# OLEDMiniFlyMCU.net
KiCad netlist of a schematic drawn in Altium Designer
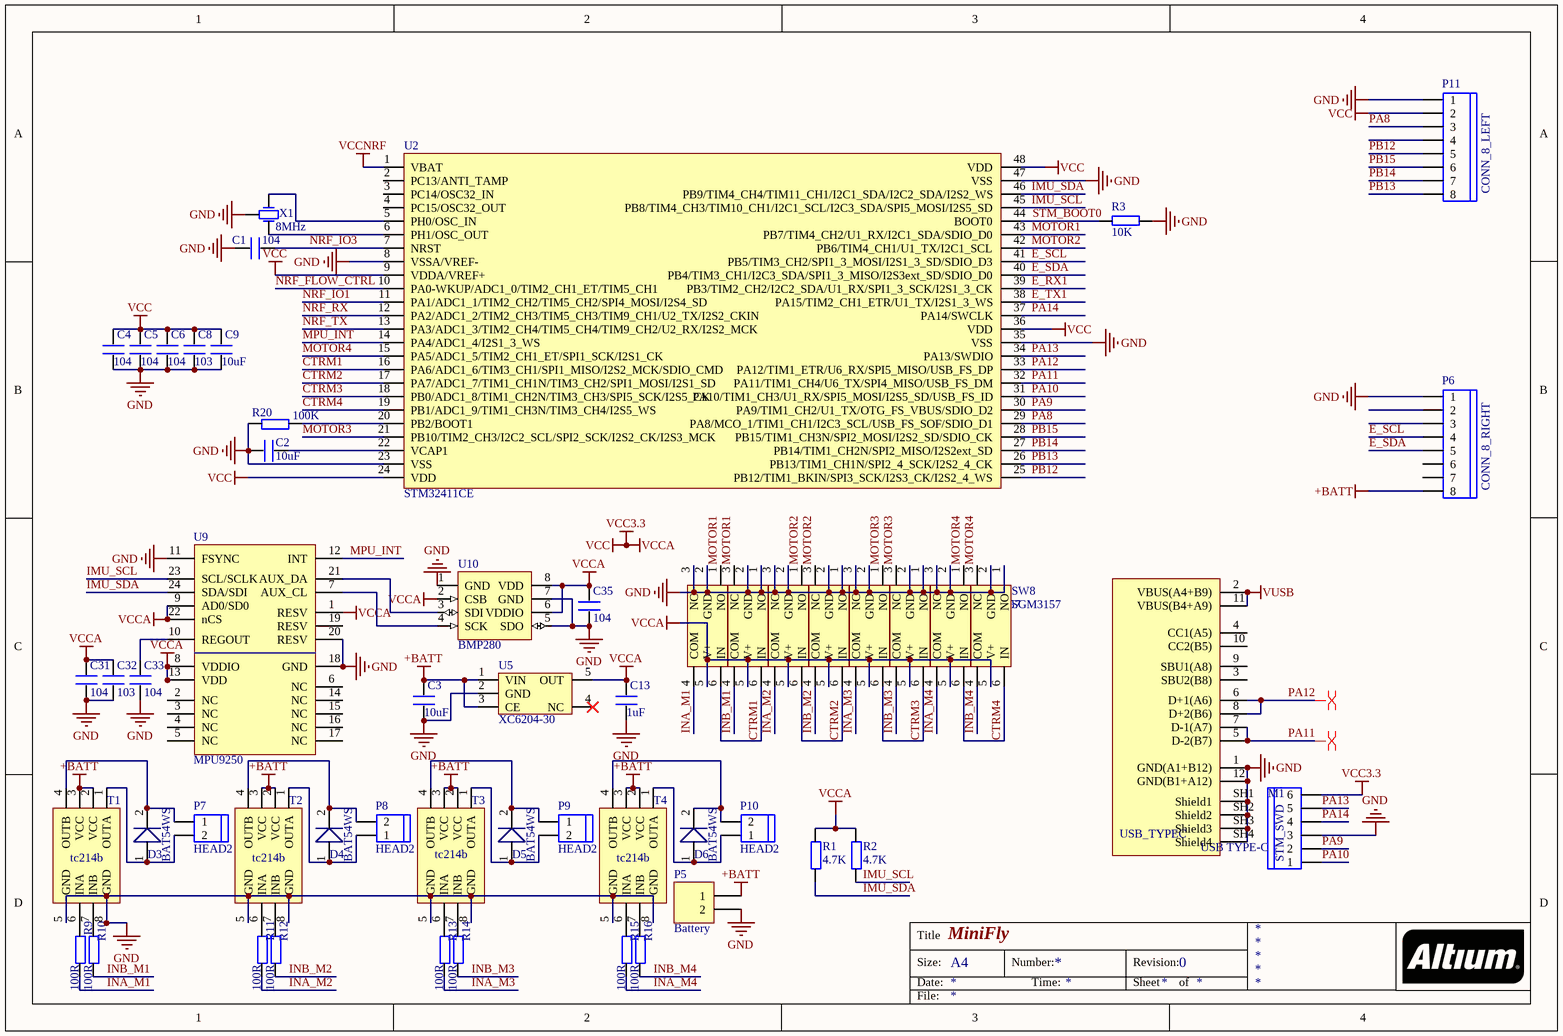
[diagram p0: OLEDMiniFlyMCU.SchDoc]

(export (version "E")
  (design (tool "Eeschema 10.0.6"))
  (components
    (comp (ref "C1") (value "104") (footprint "C 0603_L") (libsource (lib "ATK-2014-09-12") (part "C")))
    (comp (ref "C2") (value "10uF") (footprint "C 0603_L") (libsource (lib "ATK-2014-09-12") (part "C")))
    (comp (ref "C3") (value "10uF") (footprint "C 0603_L") (libsource (lib "ATK-2014-09-12") (part "C")))
    (comp (ref "C4") (value "104") (footprint "C 0603_L") (libsource (lib "ATK-2014-09-12") (part "C")))
    (comp (ref "C5") (value "104") (footprint "C 0603_L") (libsource (lib "ATK-2014-09-12") (part "C")))
    (comp (ref "C6") (value "104") (footprint "C 0603_L") (libsource (lib "ATK-2014-09-12") (part "C")))
    (comp (ref "C8") (value "103") (footprint "C 0603_L") (libsource (lib "ATK-2014-09-12") (part "C")))
    (comp (ref "C9") (value "10uF") (footprint "C 0603_L") (libsource (lib "ATK-2014-09-12") (part "C")))
    (comp (ref "C13") (value "1uF") (footprint "C 0603_L") (libsource (lib "ATK-2014-09-12") (part "C")))
    (comp (ref "C31") (value "104") (footprint "C 0603_L") (libsource (lib "ATK-2014-09-12") (part "C")))
    (comp (ref "C32") (value "103") (footprint "C 0603_L") (libsource (lib "ATK-2014-09-12") (part "C")))
    (comp (ref "C33") (value "104") (footprint "C 0603_L") (libsource (lib "ATK-2014-09-12") (part "C")))
    (comp (ref "C35") (value "104") (footprint "C 0603_L") (libsource (lib "ATK-2014-09-12") (part "C")))
    (comp (ref "D3")
      (value "BAT54WS")
      (footprint "SOD-323")
      (description "单肖特基二极管")
      (libsource (lib "ATK-2014-09-12") (part "BAT54"))
    )
    (comp (ref "D4")
      (value "BAT54WS")
      (footprint "SOD-323")
      (description "单肖特基二极管")
      (libsource (lib "ATK-2014-09-12") (part "BAT54"))
    )
    (comp (ref "D5")
      (value "BAT54WS")
      (footprint "SOD-323")
      (description "单肖特基二极管")
      (libsource (lib "ATK-2014-09-12") (part "BAT54"))
    )
    (comp (ref "D6")
      (value "BAT54WS")
      (footprint "SOD-323")
      (description "单肖特基二极管")
      (libsource (lib "ATK-2014-09-12") (part "BAT54"))
    )
    (comp (ref "M1") (value "STM_SWD") (footprint "SH1.0_6P") (libsource (lib "MiniFly ") (part "HEAD6")))
    (comp (ref "P5")
      (value "Battery")
      (footprint "HDR1X2")
      (description "Header, 2-Pin")
      (fields (field (name "PUBLISHER") "Altium Limited"))
      (libsource (lib "Miscellaneous Connectors") (part "Header 2"))
    )
    (comp (ref "P6")
      (value "CONN_8_RIGHT")
      (footprint "HEADER8-2.0MM")
      (libsource (lib "ATK-2014-09-12") (part "HEAD8"))
    )
    (comp (ref "P7")
      (value "HEAD2")
      (footprint "HEADER2-1.25MM")
      (libsource (lib "ATK-2014-09-12") (part "HEAD2"))
    )
    (comp (ref "P8")
      (value "HEAD2")
      (footprint "HEADER2-1.25MM")
      (libsource (lib "ATK-2014-09-12") (part "HEAD2"))
    )
    (comp (ref "P9")
      (value "HEAD2")
      (footprint "HEADER2-1.25MM")
      (libsource (lib "ATK-2014-09-12") (part "HEAD2"))
    )
    (comp (ref "P10")
      (value "HEAD2")
      (footprint "HEADER2-1.25MM")
      (libsource (lib "ATK-2014-09-12") (part "HEAD2"))
    )
    (comp (ref "P11")
      (value "CONN_8_LEFT")
      (footprint "HEADER8-2.0MM")
      (libsource (lib "ATK-2014-09-12") (part "HEAD8"))
    )
    (comp (ref "R1") (value "4.7K") (footprint "R 0603_L") (libsource (lib "ATK-2014-09-12") (part "R")))
    (comp (ref "R2") (value "4.7K") (footprint "R 0603_L") (libsource (lib "ATK-2014-09-12") (part "R")))
    (comp (ref "R3") (value "10K") (footprint "R 0603_L") (libsource (lib "ATK-2014-09-12") (part "R")))
    (comp (ref "R9") (value "100R") (footprint "R 0603_L") (libsource (lib "ATK-2014-09-12") (part "R")))
    (comp (ref "R10") (value "100R") (footprint "R 0603_L") (libsource (lib "ATK-2014-09-12") (part "R")))
    (comp (ref "R11") (value "100R") (footprint "R 0603_L") (libsource (lib "ATK-2014-09-12") (part "R")))
    (comp (ref "R12") (value "100R") (footprint "R 0603_L") (libsource (lib "ATK-2014-09-12") (part "R")))
    (comp (ref "R13") (value "100R") (footprint "R 0603_L") (libsource (lib "ATK-2014-09-12") (part "R")))
    (comp (ref "R14") (value "100R") (footprint "R 0603_L") (libsource (lib "ATK-2014-09-12") (part "R")))
    (comp (ref "R15") (value "100R") (footprint "R 0603_L") (libsource (lib "ATK-2014-09-12") (part "R")))
    (comp (ref "R16") (value "100R") (footprint "R 0603_L") (libsource (lib "ATK-2014-09-12") (part "R")))
    (comp (ref "R20") (value "100K") (footprint "R 0603_L") (libsource (lib "ATK-2014-09-12") (part "R")))
    (comp (ref "SW1")
      (value "SGM3157")
      (footprint "SOT363-6L")
      (description "单路双掷模拟开关")
      (libsource (lib "LovelessingSch") (part "SGM3157"))
    )
    (comp (ref "SW2")
      (value "SGM3157")
      (footprint "SOT363-6L")
      (description "单路双掷模拟开关")
      (libsource (lib "LovelessingSch") (part "SGM3157"))
    )
    (comp (ref "SW3")
      (value "SGM3157")
      (footprint "SOT363-6L")
      (description "单路双掷模拟开关")
      (libsource (lib "LovelessingSch") (part "SGM3157"))
    )
    (comp (ref "SW4")
      (value "SGM3157")
      (footprint "SOT363-6L")
      (description "单路双掷模拟开关")
      (libsource (lib "LovelessingSch") (part "SGM3157"))
    )
    (comp (ref "SW5")
      (value "SGM3157")
      (footprint "SOT363-6L")
      (description "单路双掷模拟开关")
      (libsource (lib "LovelessingSch") (part "SGM3157"))
    )
    (comp (ref "SW6")
      (value "SGM3157")
      (footprint "SOT363-6L")
      (description "单路双掷模拟开关")
      (libsource (lib "LovelessingSch") (part "SGM3157"))
    )
    (comp (ref "SW7")
      (value "SGM3157")
      (footprint "SOT363-6L")
      (description "单路双掷模拟开关")
      (libsource (lib "LovelessingSch") (part "SGM3157"))
    )
    (comp (ref "SW8")
      (value "SGM3157")
      (footprint "SOT363-6L")
      (description "单路双掷模拟开关")
      (libsource (lib "LovelessingSch") (part "SGM3157"))
    )
    (comp (ref "T1")
      (value "tc214b")
      (footprint "SOP8_L")
      (description "马达驱动芯片")
      (libsource (lib "LovelessingSch") (part "tc214b"))
    )
    (comp (ref "T2")
      (value "tc214b")
      (footprint "SOP8_L")
      (description "马达驱动芯片")
      (libsource (lib "LovelessingSch") (part "tc214b"))
    )
    (comp (ref "T3")
      (value "tc214b")
      (footprint "SOP8_L")
      (description "马达驱动芯片")
      (libsource (lib "LovelessingSch") (part "tc214b"))
    )
    (comp (ref "T4")
      (value "tc214b")
      (footprint "SOP8_L")
      (description "马达驱动芯片")
      (libsource (lib "LovelessingSch") (part "tc214b"))
    )
    (comp (ref "U2")
      (value "STM32411CE")
      (footprint "UFQFPN48")
      (description "STM32411xC_xE")
      (libsource (lib "ATK-2014-09-12") (part "STM32F411xC_xE"))
    )
    (comp (ref "U5")
      (value "XC6204-30")
      (footprint "SOT23-5L")
      (libsource (lib "ATK-2014-09-12") (part "XC6204"))
    )
    (comp (ref "U9")
      (value "MPU9250")
      (footprint "MPU9250")
      (description "9轴陀螺仪")
      (libsource (lib "LovelessingSch") (part "MPU9250"))
    )
    (comp (ref "U10")
      (value "BMP280")
      (footprint "LGA-8")
      (description "气压传感器")
      (libsource (lib "LovelessingSch") (part "BMP280"))
    )
    (comp (ref "USB_TYPEC")
      (value "USB TypeC")
      (footprint "USB Type-C")
      (description "12P TypeC 母座")
      (libsource (lib "ESP32_Weather") (part "USB Type-C"))
    )
    (comp (ref "X1")
      (value "8MHz")
      (footprint "XTAL-3215-3P")
      (libsource (lib "ATK-2014-09-12") (part "XTAL-3215"))
    )
  )
  (nets
    (net (code "1") (name "+BATT") (class "Default")
      (node (ref "C3") (pin "2") (pintype "passive"))
      (node (ref "P5") (pin "1") (pinfunction "1_1") (pintype "passive"))
      (node (ref "P6") (pin "8") (pinfunction "8_8") (pintype "passive"))
      (node (ref "T1") (pin "2") (pinfunction "VCC_2") (pintype "passive"))
      (node (ref "T1") (pin "3") (pinfunction "VCC_3") (pintype "passive"))
      (node (ref "T2") (pin "2") (pinfunction "VCC_2") (pintype "passive"))
      (node (ref "T2") (pin "3") (pinfunction "VCC_3") (pintype "passive"))
      (node (ref "T3") (pin "2") (pinfunction "VCC_2") (pintype "passive"))
      (node (ref "T3") (pin "3") (pinfunction "VCC_3") (pintype "passive"))
      (node (ref "T4") (pin "2") (pinfunction "VCC_2") (pintype "passive"))
      (node (ref "T4") (pin "3") (pinfunction "VCC_3") (pintype "passive"))
      (node (ref "U5") (pin "1") (pinfunction "VIN_1") (pintype "passive"))
      (node (ref "U5") (pin "3") (pinfunction "CE_3") (pintype "passive"))
    )
    (net (code "2") (name "/CTRM1") (class "Default")
      (node (ref "SW1") (pin "6") (pinfunction "IN_6") (pintype "passive"))
      (node (ref "SW2") (pin "6") (pinfunction "IN_6") (pintype "passive"))
      (node (ref "U2") (pin "16") (pinfunction "PA6/ADC1_6/TIM3_CH1/SPI1_MISO/I2S2_MCK/SDIO_CMD_16") (pintype "passive"))
    )
    (net (code "3") (name "/CTRM2") (class "Default")
      (node (ref "SW3") (pin "6") (pinfunction "IN_6") (pintype "passive"))
      (node (ref "SW4") (pin "6") (pinfunction "IN_6") (pintype "passive"))
      (node (ref "U2") (pin "17") (pinfunction "PA7/ADC1_7/TIM1_CH1N/TIM3_CH2/SPI1_MOSI/I2S1_SD_17") (pintype "passive"))
    )
    (net (code "4") (name "/CTRM3") (class "Default")
      (node (ref "SW5") (pin "6") (pinfunction "IN_6") (pintype "passive"))
      (node (ref "SW6") (pin "6") (pinfunction "IN_6") (pintype "passive"))
      (node (ref "U2") (pin "18") (pinfunction "PB0/ADC1_8/TIM1_CH2N/TIM3_CH3/SPI5_SCK/I2S5_CK_18") (pintype "passive"))
    )
    (net (code "5") (name "/CTRM4") (class "Default")
      (node (ref "SW7") (pin "6") (pinfunction "IN_6") (pintype "passive"))
      (node (ref "SW8") (pin "6") (pinfunction "IN_6") (pintype "passive"))
      (node (ref "U2") (pin "19") (pinfunction "PB1/ADC1_9/TIM1_CH3N/TIM3_CH4/I2S5_WS_19") (pintype "passive"))
    )
    (net (code "6") (name "/E_RX1") (class "Default")
      (node (ref "U2") (pin "39") (pinfunction "PB3/TIM2_CH2/I2C2_SDA/U1_RX/SPI1_3_SCK/I2S1_3_CK_39") (pintype "passive"))
    )
    (net (code "7") (name "/E_SCL") (class "Default")
      (node (ref "P6") (pin "4") (pinfunction "4_4") (pintype "passive"))
      (node (ref "U2") (pin "41") (pinfunction "PB5/TIM3_CH2/SPI1_3_MOSI/I2S1_3_SD/SDIO_D3_41") (pintype "passive"))
    )
    (net (code "8") (name "/E_SDA") (class "Default")
      (node (ref "P6") (pin "5") (pinfunction "5_5") (pintype "passive"))
      (node (ref "U2") (pin "40") (pinfunction "PB4/TIM3_CH1/I2C3_SDA/SPI1_3_MISO/I2S3ext_SD/SDIO_D0_40") (pintype "passive"))
    )
    (net (code "9") (name "/E_TX1") (class "Default")
      (node (ref "U2") (pin "38") (pinfunction "PA15/TIM2_CH1_ETR/U1_TX/I2S1_3_WS_38") (pintype "passive"))
    )
    (net (code "10") (name "/IMU_SCL") (class "Default")
      (node (ref "R2") (pin "1") (pintype "passive"))
      (node (ref "U2") (pin "45") (pinfunction "PB8/TIM4_CH3/TIM10_CH1/I2C1_SCL/I2C3_SDA/SPI5_MOSI/I2S5_SD_45") (pintype "passive"))
      (node (ref "U9") (pin "23") (pinfunction "SCL/SCLK_23") (pintype "passive"))
    )
    (net (code "11") (name "/IMU_SDA") (class "Default")
      (node (ref "R1") (pin "1") (pintype "passive"))
      (node (ref "U2") (pin "46") (pinfunction "PB9/TIM4_CH4/TIM11_CH1/I2C1_SDA/I2C2_SDA/I2S2_WS_46") (pintype "passive"))
      (node (ref "U9") (pin "24") (pinfunction "SDA/SDI_24") (pintype "passive"))
    )
    (net (code "12") (name "/INA_M1") (class "Default")
      (node (ref "R9") (pin "1") (pintype "passive"))
      (node (ref "SW1") (pin "4") (pinfunction "COM_4") (pintype "passive"))
    )
    (net (code "13") (name "/INA_M2") (class "Default")
      (node (ref "R11") (pin "1") (pintype "passive"))
      (node (ref "SW3") (pin "4") (pinfunction "COM_4") (pintype "passive"))
    )
    (net (code "14") (name "/INA_M3") (class "Default")
      (node (ref "R13") (pin "1") (pintype "passive"))
      (node (ref "SW5") (pin "4") (pinfunction "COM_4") (pintype "passive"))
    )
    (net (code "15") (name "/INA_M4") (class "Default")
      (node (ref "R15") (pin "1") (pintype "passive"))
      (node (ref "SW7") (pin "4") (pinfunction "COM_4") (pintype "passive"))
    )
    (net (code "16") (name "/INB_M1") (class "Default")
      (node (ref "R10") (pin "1") (pintype "passive"))
      (node (ref "SW2") (pin "4") (pinfunction "COM_4") (pintype "passive"))
    )
    (net (code "17") (name "/INB_M2") (class "Default")
      (node (ref "R12") (pin "1") (pintype "passive"))
      (node (ref "SW4") (pin "4") (pinfunction "COM_4") (pintype "passive"))
    )
    (net (code "18") (name "/INB_M3") (class "Default")
      (node (ref "R14") (pin "1") (pintype "passive"))
      (node (ref "SW6") (pin "4") (pinfunction "COM_4") (pintype "passive"))
    )
    (net (code "19") (name "/INB_M4") (class "Default")
      (node (ref "R16") (pin "1") (pintype "passive"))
      (node (ref "SW8") (pin "4") (pinfunction "COM_4") (pintype "passive"))
    )
    (net (code "20") (name "/MOTOR1") (class "Default")
      (node (ref "SW1") (pin "1") (pinfunction "NO_1") (pintype "passive"))
      (node (ref "SW2") (pin "3") (pinfunction "NC_3") (pintype "passive"))
      (node (ref "U2") (pin "43") (pinfunction "PB7/TIM4_CH2/U1_RX/I2C1_SDA/SDIO_D0_43") (pintype "passive"))
    )
    (net (code "21") (name "/MOTOR2") (class "Default")
      (node (ref "SW3") (pin "1") (pinfunction "NO_1") (pintype "passive"))
      (node (ref "SW4") (pin "3") (pinfunction "NC_3") (pintype "passive"))
      (node (ref "U2") (pin "42") (pinfunction "PB6/TIM4_CH1/U1_TX/I2C1_SCL_42") (pintype "passive"))
    )
    (net (code "22") (name "/MOTOR3") (class "Default")
      (node (ref "SW5") (pin "1") (pinfunction "NO_1") (pintype "passive"))
      (node (ref "SW6") (pin "3") (pinfunction "NC_3") (pintype "passive"))
      (node (ref "U2") (pin "21") (pinfunction "PB10/TIM2_CH3/I2C2_SCL/SPI2_SCK/I2S2_CK/I2S3_MCK_21") (pintype "passive"))
    )
    (net (code "23") (name "/MOTOR4") (class "Default")
      (node (ref "SW7") (pin "1") (pinfunction "NO_1") (pintype "passive"))
      (node (ref "SW8") (pin "3") (pinfunction "NC_3") (pintype "passive"))
      (node (ref "U2") (pin "15") (pinfunction "PA5/ADC1_5/TIM2_CH1_ET/SPI1_SCK/I2S1_CK_15") (pintype "passive"))
    )
    (net (code "24") (name "/MPU_INT") (class "Default")
      (node (ref "U2") (pin "14") (pinfunction "PA4/ADC1_4/I2S1_3_WS_14") (pintype "passive"))
      (node (ref "U9") (pin "12") (pinfunction "INT_12") (pintype "passive"))
    )
    (net (code "25") (name "/NRF_FLOW_CTRL") (class "Default")
      (node (ref "U2") (pin "10") (pinfunction "PA0-WKUP/ADC1_0/TIM2_CH1_ET/TIM5_CH1_10") (pintype "passive"))
    )
    (net (code "26") (name "/NRF_IO1") (class "Default")
      (node (ref "U2") (pin "11") (pinfunction "PA1/ADC1_1/TIM2_CH2/TIM5_CH2/SPI4_MOSI/I2S4_SD_11") (pintype "passive"))
    )
    (net (code "27") (name "/NRF_IO3") (class "Default")
      (node (ref "C1") (pin "1") (pintype "passive"))
      (node (ref "U2") (pin "7") (pinfunction "NRST_7") (pintype "passive"))
    )
    (net (code "28") (name "/NRF_RX") (class "Default")
      (node (ref "U2") (pin "12") (pinfunction "PA2/ADC1_2/TIM2_CH3/TIM5_CH3/TIM9_CH1/U2_TX/I2S2_CKIN_12") (pintype "passive"))
    )
    (net (code "29") (name "/NRF_TX") (class "Default")
      (node (ref "U2") (pin "13") (pinfunction "PA3/ADC1_3/TIM2_CH4/TIM5_CH4/TIM9_CH2/U2_RX/I2S2_MCK_13") (pintype "passive"))
    )
    (net (code "30") (name "/PA8") (class "Default")
      (node (ref "P11") (pin "3") (pinfunction "3_3") (pintype "passive"))
      (node (ref "U2") (pin "29") (pinfunction "PA8/MCO_1/TIM1_CH1/I2C3_SCL/USB_FS_SOF/SDIO_D1_29") (pintype "passive"))
    )
    (net (code "31") (name "/PA9") (class "Default")
      (node (ref "M1") (pin "2") (pinfunction "2_2") (pintype "passive"))
      (node (ref "U2") (pin "30") (pinfunction "PA9/TIM1_CH2/U1_TX/OTG_FS_VBUS/SDIO_D2_30") (pintype "passive"))
    )
    (net (code "32") (name "/PA10") (class "Default")
      (node (ref "M1") (pin "1") (pinfunction "1_1") (pintype "passive"))
      (node (ref "U2") (pin "31") (pinfunction "PA10/TIM1_CH3/U1_RX/SPI5_MOSI/I2S5_SD/USB_FS_ID_31") (pintype "passive"))
    )
    (net (code "33") (name "/PA11") (class "Default")
      (node (ref "U2") (pin "32") (pinfunction "PA11/TIM1_CH4/U6_TX/SPI4_MISO/USB_FS_DM_32") (pintype "passive"))
      (node (ref "USB_TYPEC") (pin "5") (pinfunction "D-2(B7)_5") (pintype "passive"))
      (node (ref "USB_TYPEC") (pin "7") (pinfunction "D-1(A7)_7") (pintype "passive"))
    )
    (net (code "34") (name "/PA12") (class "Default")
      (node (ref "U2") (pin "33") (pinfunction "PA12/TIM1_ETR/U6_RX/SPI5_MISO/USB_FS_DP_33") (pintype "passive"))
      (node (ref "USB_TYPEC") (pin "6") (pinfunction "D+1(A6)_6") (pintype "passive"))
      (node (ref "USB_TYPEC") (pin "8") (pinfunction "D+2(B6)_8") (pintype "passive"))
    )
    (net (code "35") (name "/PA13") (class "Default")
      (node (ref "M1") (pin "5") (pinfunction "5_5") (pintype "passive"))
      (node (ref "U2") (pin "34") (pinfunction "PA13/SWDIO_34") (pintype "passive"))
    )
    (net (code "36") (name "/PA14") (class "Default")
      (node (ref "M1") (pin "4") (pinfunction "4_4") (pintype "passive"))
      (node (ref "U2") (pin "37") (pinfunction "PA14/SWCLK_37") (pintype "passive"))
    )
    (net (code "37") (name "/PB12") (class "Default")
      (node (ref "P11") (pin "5") (pinfunction "5_5") (pintype "passive"))
      (node (ref "U2") (pin "25") (pinfunction "PB12/TIM1_BKIN/SPI3_SCK/I2S3_CK/I2S2_4_WS_25") (pintype "passive"))
    )
    (net (code "38") (name "/PB13") (class "Default")
      (node (ref "P11") (pin "8") (pinfunction "8_8") (pintype "passive"))
      (node (ref "U2") (pin "26") (pinfunction "PB13/TIM1_CH1N/SPI2_4_SCK/I2S2_4_CK_26") (pintype "passive"))
    )
    (net (code "39") (name "/PB14") (class "Default")
      (node (ref "P11") (pin "7") (pinfunction "7_7") (pintype "passive"))
      (node (ref "U2") (pin "27") (pinfunction "PB14/TIM1_CH2N/SPI2_MISO/I2S2ext_SD_27") (pintype "passive"))
    )
    (net (code "40") (name "/PB15") (class "Default")
      (node (ref "P11") (pin "6") (pinfunction "6_6") (pintype "passive"))
      (node (ref "U2") (pin "28") (pinfunction "PB15/TIM1_CH3N/SPI2_MOSI/I2S2_SD/SDIO_CK_28") (pintype "passive"))
    )
    (net (code "41") (name "/STM_BOOT0") (class "Default")
      (node (ref "R3") (pin "2") (pintype "passive"))
      (node (ref "U2") (pin "44") (pinfunction "BOOT0_44") (pintype "passive"))
    )
    (net (code "42") (name "GND") (class "Default")
      (node (ref "C1") (pin "2") (pintype "passive"))
      (node (ref "C13") (pin "1") (pintype "passive"))
      (node (ref "C2") (pin "1") (pintype "passive"))
      (node (ref "C3") (pin "1") (pintype "passive"))
      (node (ref "C31") (pin "1") (pintype "passive"))
      (node (ref "C32") (pin "1") (pintype "passive"))
      (node (ref "C33") (pin "1") (pintype "passive"))
      (node (ref "C35") (pin "1") (pintype "passive"))
      (node (ref "C4") (pin "1") (pintype "passive"))
      (node (ref "C5") (pin "1") (pintype "passive"))
      (node (ref "C6") (pin "1") (pintype "passive"))
      (node (ref "C8") (pin "1") (pintype "passive"))
      (node (ref "C9") (pin "1") (pintype "passive"))
      (node (ref "M1") (pin "3") (pinfunction "3_3") (pintype "passive"))
      (node (ref "P11") (pin "1") (pinfunction "1_1") (pintype "passive"))
      (node (ref "P5") (pin "2") (pinfunction "2_2") (pintype "passive"))
      (node (ref "P6") (pin "1") (pinfunction "1_1") (pintype "passive"))
      (node (ref "R20") (pin "1") (pintype "passive"))
      (node (ref "R3") (pin "1") (pintype "passive"))
      (node (ref "SW1") (pin "2") (pinfunction "GND_2") (pintype "passive"))
      (node (ref "SW1") (pin "3") (pinfunction "NC_3") (pintype "passive"))
      (node (ref "SW2") (pin "1") (pinfunction "NO_1") (pintype "passive"))
      (node (ref "SW2") (pin "2") (pinfunction "GND_2") (pintype "passive"))
      (node (ref "SW3") (pin "2") (pinfunction "GND_2") (pintype "passive"))
      (node (ref "SW3") (pin "3") (pinfunction "NC_3") (pintype "passive"))
      (node (ref "SW4") (pin "1") (pinfunction "NO_1") (pintype "passive"))
      (node (ref "SW4") (pin "2") (pinfunction "GND_2") (pintype "passive"))
      (node (ref "SW5") (pin "2") (pinfunction "GND_2") (pintype "passive"))
      (node (ref "SW5") (pin "3") (pinfunction "NC_3") (pintype "passive"))
      (node (ref "SW6") (pin "1") (pinfunction "NO_1") (pintype "passive"))
      (node (ref "SW6") (pin "2") (pinfunction "GND_2") (pintype "passive"))
      (node (ref "SW7") (pin "2") (pinfunction "GND_2") (pintype "passive"))
      (node (ref "SW7") (pin "3") (pinfunction "NC_3") (pintype "passive"))
      (node (ref "SW8") (pin "1") (pinfunction "NO_1") (pintype "passive"))
      (node (ref "SW8") (pin "2") (pinfunction "GND_2") (pintype "passive"))
      (node (ref "T1") (pin "5") (pinfunction "GND_5") (pintype "passive"))
      (node (ref "T1") (pin "8") (pinfunction "GND_8") (pintype "passive"))
      (node (ref "T2") (pin "5") (pinfunction "GND_5") (pintype "passive"))
      (node (ref "T2") (pin "8") (pinfunction "GND_8") (pintype "passive"))
      (node (ref "T3") (pin "5") (pinfunction "GND_5") (pintype "passive"))
      (node (ref "T3") (pin "8") (pinfunction "GND_8") (pintype "passive"))
      (node (ref "T4") (pin "5") (pinfunction "GND_5") (pintype "passive"))
      (node (ref "T4") (pin "8") (pinfunction "GND_8") (pintype "passive"))
      (node (ref "U10") (pin "1") (pinfunction "GND_1") (pintype "passive"))
      (node (ref "U10") (pin "5") (pinfunction "SDO_5") (pintype "bidirectional"))
      (node (ref "U10") (pin "7") (pinfunction "GND_7") (pintype "power_in"))
      (node (ref "U2") (pin "23") (pinfunction "VSS_23") (pintype "passive"))
      (node (ref "U2") (pin "35") (pinfunction "VSS_35") (pintype "passive"))
      (node (ref "U2") (pin "47") (pinfunction "VSS_47") (pintype "passive"))
      (node (ref "U2") (pin "8") (pinfunction "VSSA/VREF-_8") (pintype "passive"))
      (node (ref "U5") (pin "2") (pinfunction "GND_2") (pintype "passive"))
      (node (ref "U9") (pin "11") (pinfunction "FSYNC_11") (pintype "passive"))
      (node (ref "U9") (pin "18") (pinfunction "GND_18") (pintype "passive"))
      (node (ref "U9") (pin "20") (pinfunction "RESV_20") (pintype "passive"))
      (node (ref "USB_TYPEC") (pin "1") (pinfunction "GND(A1+B12)_1") (pintype "passive"))
      (node (ref "USB_TYPEC") (pin "12") (pinfunction "GND(B1+A12)_12") (pintype "passive"))
      (node (ref "USB_TYPEC") (pin "SH1") (pinfunction "Shield1_SH1") (pintype "passive"))
      (node (ref "USB_TYPEC") (pin "SH2") (pinfunction "Shield2_SH2") (pintype "passive"))
      (node (ref "USB_TYPEC") (pin "SH3") (pinfunction "Shield3_SH3") (pintype "passive"))
      (node (ref "USB_TYPEC") (pin "SH4") (pinfunction "Shield4_SH4") (pintype "passive"))
      (node (ref "X1") (pin "2") (pinfunction "GND_2") (pintype "passive"))
    )
    (net (code "43") (name "Net-(T1-INA)") (class "Default")
      (node (ref "R9") (pin "2") (pintype "passive"))
      (node (ref "T1") (pin "6") (pinfunction "INA_6") (pintype "passive"))
    )
    (net (code "44") (name "Net-(T1-INB)") (class "Default")
      (node (ref "R10") (pin "2") (pintype "passive"))
      (node (ref "T1") (pin "7") (pinfunction "INB_7") (pintype "passive"))
    )
    (net (code "45") (name "Net-(T1-OUTA)") (class "Default")
      (node (ref "D3") (pin "1") (pinfunction "1_1") (pintype "passive"))
      (node (ref "P7") (pin "2") (pinfunction "2_2") (pintype "passive"))
      (node (ref "T1") (pin "1") (pinfunction "OUTA_1") (pintype "passive"))
    )
    (net (code "46") (name "Net-(T1-OUTB)") (class "Default")
      (node (ref "D3") (pin "2") (pinfunction "2_2") (pintype "passive"))
      (node (ref "P7") (pin "1") (pinfunction "1_1") (pintype "passive"))
      (node (ref "T1") (pin "4") (pinfunction "OUTB_4") (pintype "passive"))
    )
    (net (code "47") (name "Net-(T2-INA)") (class "Default")
      (node (ref "R11") (pin "2") (pintype "passive"))
      (node (ref "T2") (pin "6") (pinfunction "INA_6") (pintype "passive"))
    )
    (net (code "48") (name "Net-(T2-INB)") (class "Default")
      (node (ref "R12") (pin "2") (pintype "passive"))
      (node (ref "T2") (pin "7") (pinfunction "INB_7") (pintype "passive"))
    )
    (net (code "49") (name "Net-(T2-OUTA)") (class "Default")
      (node (ref "D4") (pin "1") (pinfunction "1_1") (pintype "passive"))
      (node (ref "P8") (pin "1") (pinfunction "1_1") (pintype "passive"))
      (node (ref "T2") (pin "1") (pinfunction "OUTA_1") (pintype "passive"))
    )
    (net (code "50") (name "Net-(T2-OUTB)") (class "Default")
      (node (ref "D4") (pin "2") (pinfunction "2_2") (pintype "passive"))
      (node (ref "P8") (pin "2") (pinfunction "2_2") (pintype "passive"))
      (node (ref "T2") (pin "4") (pinfunction "OUTB_4") (pintype "passive"))
    )
    (net (code "51") (name "Net-(T3-INA)") (class "Default")
      (node (ref "R13") (pin "2") (pintype "passive"))
      (node (ref "T3") (pin "6") (pinfunction "INA_6") (pintype "passive"))
    )
    (net (code "52") (name "Net-(T3-INB)") (class "Default")
      (node (ref "R14") (pin "2") (pintype "passive"))
      (node (ref "T3") (pin "7") (pinfunction "INB_7") (pintype "passive"))
    )
    (net (code "53") (name "Net-(T3-OUTA)") (class "Default")
      (node (ref "D5") (pin "1") (pinfunction "1_1") (pintype "passive"))
      (node (ref "P9") (pin "2") (pinfunction "2_2") (pintype "passive"))
      (node (ref "T3") (pin "1") (pinfunction "OUTA_1") (pintype "passive"))
    )
    (net (code "54") (name "Net-(T3-OUTB)") (class "Default")
      (node (ref "D5") (pin "2") (pinfunction "2_2") (pintype "passive"))
      (node (ref "P9") (pin "1") (pinfunction "1_1") (pintype "passive"))
      (node (ref "T3") (pin "4") (pinfunction "OUTB_4") (pintype "passive"))
    )
    (net (code "55") (name "Net-(T4-INA)") (class "Default")
      (node (ref "R15") (pin "2") (pintype "passive"))
      (node (ref "T4") (pin "6") (pinfunction "INA_6") (pintype "passive"))
    )
    (net (code "56") (name "Net-(T4-INB)") (class "Default")
      (node (ref "R16") (pin "2") (pintype "passive"))
      (node (ref "T4") (pin "7") (pinfunction "INB_7") (pintype "passive"))
    )
    (net (code "57") (name "Net-(T4-OUTA)") (class "Default")
      (node (ref "D6") (pin "1") (pinfunction "1_1") (pintype "passive"))
      (node (ref "P10") (pin "1") (pinfunction "1_1") (pintype "passive"))
      (node (ref "T4") (pin "1") (pinfunction "OUTA_1") (pintype "passive"))
    )
    (net (code "58") (name "Net-(T4-OUTB)") (class "Default")
      (node (ref "D6") (pin "2") (pinfunction "2_2") (pintype "passive"))
      (node (ref "P10") (pin "2") (pinfunction "2_2") (pintype "passive"))
      (node (ref "T4") (pin "4") (pinfunction "OUTB_4") (pintype "passive"))
    )
    (net (code "59") (name "Net-(U2-PB2{slash}BOOT1)") (class "Default")
      (node (ref "R20") (pin "2") (pintype "passive"))
      (node (ref "U2") (pin "20") (pinfunction "PB2/BOOT1_20") (pintype "passive"))
    )
    (net (code "60") (name "Net-(U2-PH0{slash}OSC_IN)") (class "Default")
      (node (ref "U2") (pin "5") (pinfunction "PH0/OSC_IN_5") (pintype "passive"))
      (node (ref "X1") (pin "1") (pinfunction "OSC1_1") (pintype "passive"))
    )
    (net (code "61") (name "Net-(U2-PH1{slash}OSC_OUT)") (class "Default")
      (node (ref "U2") (pin "6") (pinfunction "PH1/OSC_OUT_6") (pintype "passive"))
      (node (ref "X1") (pin "3") (pinfunction "OSC2_3") (pintype "passive"))
    )
    (net (code "62") (name "Net-(U2-VCAP1)") (class "Default")
      (node (ref "C2") (pin "2") (pintype "passive"))
      (node (ref "U2") (pin "22") (pinfunction "VCAP1_22") (pintype "passive"))
    )
    (net (code "63") (name "Net-(U9-REGOUT)") (class "Default")
      (node (ref "C33") (pin "2") (pintype "passive"))
      (node (ref "U9") (pin "10") (pinfunction "REGOUT_10") (pintype "passive"))
    )
    (net (code "64") (name "Net-(U10-SCK)") (class "Default")
      (node (ref "U10") (pin "4") (pinfunction "SCK_4") (pintype "input"))
      (node (ref "U9") (pin "7") (pinfunction "AUX_CL_7") (pintype "passive"))
    )
    (net (code "65") (name "Net-(U10-SDI)") (class "Default")
      (node (ref "U10") (pin "3") (pinfunction "SDI_3") (pintype "bidirectional"))
      (node (ref "U9") (pin "21") (pinfunction "AUX_DA_21") (pintype "passive"))
    )
    (net (code "66") (name "VCC") (class "Default")
      (node (ref "C13") (pin "2") (pintype "passive"))
      (node (ref "C31") (pin "2") (pintype "passive"))
      (node (ref "C32") (pin "2") (pintype "passive"))
      (node (ref "C35") (pin "2") (pintype "passive"))
      (node (ref "C4") (pin "2") (pintype "passive"))
      (node (ref "C5") (pin "2") (pintype "passive"))
      (node (ref "C6") (pin "2") (pintype "passive"))
      (node (ref "C8") (pin "2") (pintype "passive"))
      (node (ref "C9") (pin "2") (pintype "passive"))
      (node (ref "M1") (pin "6") (pinfunction "6_6") (pintype "passive"))
      (node (ref "P11") (pin "2") (pinfunction "2_2") (pintype "passive"))
      (node (ref "R1") (pin "2") (pintype "passive"))
      (node (ref "R2") (pin "2") (pintype "passive"))
      (node (ref "SW1") (pin "5") (pinfunction "V+_5") (pintype "passive"))
      (node (ref "SW2") (pin "5") (pinfunction "V+_5") (pintype "passive"))
      (node (ref "SW3") (pin "5") (pinfunction "V+_5") (pintype "passive"))
      (node (ref "SW4") (pin "5") (pinfunction "V+_5") (pintype "passive"))
      (node (ref "SW5") (pin "5") (pinfunction "V+_5") (pintype "passive"))
      (node (ref "SW6") (pin "5") (pinfunction "V+_5") (pintype "passive"))
      (node (ref "SW7") (pin "5") (pinfunction "V+_5") (pintype "passive"))
      (node (ref "SW8") (pin "5") (pinfunction "V+_5") (pintype "passive"))
      (node (ref "U10") (pin "2") (pinfunction "CSB_2") (pintype "input"))
      (node (ref "U10") (pin "6") (pinfunction "VDDIO_6") (pintype "power_in"))
      (node (ref "U10") (pin "8") (pinfunction "VDD_8") (pintype "power_in"))
      (node (ref "U2") (pin "24") (pinfunction "VDD_24") (pintype "passive"))
      (node (ref "U2") (pin "36") (pinfunction "VDD_36") (pintype "passive"))
      (node (ref "U2") (pin "48") (pinfunction "VDD_48") (pintype "passive"))
      (node (ref "U2") (pin "9") (pinfunction "VDDA/VREF+_9") (pintype "passive"))
      (node (ref "U5") (pin "5") (pinfunction "OUT_5") (pintype "passive"))
      (node (ref "U9") (pin "1") (pinfunction "RESV_1") (pintype "passive"))
      (node (ref "U9") (pin "13") (pinfunction "VDD_13") (pintype "passive"))
      (node (ref "U9") (pin "22") (pinfunction "nCS_22") (pintype "passive"))
      (node (ref "U9") (pin "8") (pinfunction "VDDIO_8") (pintype "passive"))
      (node (ref "U9") (pin "9") (pinfunction "AD0/SD0_9") (pintype "passive"))
    )
    (net (code "67") (name "VCCNRF") (class "Default")
      (node (ref "U2") (pin "1") (pinfunction "VBAT_1") (pintype "passive"))
    )
    (net (code "68") (name "VUSB") (class "Default")
      (node (ref "USB_TYPEC") (pin "11") (pinfunction "VBUS(B4+A9)_11") (pintype "passive"))
      (node (ref "USB_TYPEC") (pin "2") (pinfunction "VBUS(A4+B9)_2") (pintype "passive"))
    )
    (net (code "69") (name "unconnected-(P6-Pad2)") (class "Default")
      (node (ref "P6") (pin "2") (pinfunction "2_2") (pintype "passive"))
    )
    (net (code "70") (name "unconnected-(P6-Pad3)") (class "Default")
      (node (ref "P6") (pin "3") (pinfunction "3_3") (pintype "passive"))
    )
    (net (code "71") (name "unconnected-(P6-Pad6)") (class "Default")
      (node (ref "P6") (pin "6") (pinfunction "6_6") (pintype "passive"))
    )
    (net (code "72") (name "unconnected-(P6-Pad7)") (class "Default")
      (node (ref "P6") (pin "7") (pinfunction "7_7") (pintype "passive"))
    )
    (net (code "73") (name "unconnected-(P11-Pad4)") (class "Default")
      (node (ref "P11") (pin "4") (pinfunction "4_4") (pintype "passive"))
    )
    (net (code "74") (name "unconnected-(U2-PC13{slash}ANTI_TAMP-Pad2)") (class "Default")
      (node (ref "U2") (pin "2") (pinfunction "PC13/ANTI_TAMP_2") (pintype "passive"))
    )
    (net (code "75") (name "unconnected-(U2-PC14{slash}OSC32_IN-Pad3)") (class "Default")
      (node (ref "U2") (pin "3") (pinfunction "PC14/OSC32_IN_3") (pintype "passive"))
    )
    (net (code "76") (name "unconnected-(U2-PC15{slash}OSC32_OUT-Pad4)") (class "Default")
      (node (ref "U2") (pin "4") (pinfunction "PC15/OSC32_OUT_4") (pintype "passive"))
    )
    (net (code "77") (name "unconnected-(U5-NC-Pad4)") (class "Default")
      (node (ref "U5") (pin "4") (pinfunction "NC_4") (pintype "passive+no_connect"))
    )
    (net (code "78") (name "unconnected-(U9-NC-Pad2)") (class "Default")
      (node (ref "U9") (pin "2") (pinfunction "NC_2") (pintype "passive"))
    )
    (net (code "79") (name "unconnected-(U9-NC-Pad3)") (class "Default")
      (node (ref "U9") (pin "3") (pinfunction "NC_3") (pintype "passive"))
    )
    (net (code "80") (name "unconnected-(U9-NC-Pad4)") (class "Default")
      (node (ref "U9") (pin "4") (pinfunction "NC_4") (pintype "passive"))
    )
    (net (code "81") (name "unconnected-(U9-NC-Pad5)") (class "Default")
      (node (ref "U9") (pin "5") (pinfunction "NC_5") (pintype "passive"))
    )
    (net (code "82") (name "unconnected-(U9-NC-Pad6)") (class "Default")
      (node (ref "U9") (pin "6") (pinfunction "NC_6") (pintype "passive"))
    )
    (net (code "83") (name "unconnected-(U9-NC-Pad14)") (class "Default")
      (node (ref "U9") (pin "14") (pinfunction "NC_14") (pintype "passive"))
    )
    (net (code "84") (name "unconnected-(U9-NC-Pad15)") (class "Default")
      (node (ref "U9") (pin "15") (pinfunction "NC_15") (pintype "passive"))
    )
    (net (code "85") (name "unconnected-(U9-NC-Pad16)") (class "Default")
      (node (ref "U9") (pin "16") (pinfunction "NC_16") (pintype "passive"))
    )
    (net (code "86") (name "unconnected-(U9-NC-Pad17)") (class "Default")
      (node (ref "U9") (pin "17") (pinfunction "NC_17") (pintype "passive"))
    )
    (net (code "87") (name "unconnected-(U9-RESV-Pad19)") (class "Default")
      (node (ref "U9") (pin "19") (pinfunction "RESV_19") (pintype "passive"))
    )
    (net (code "88") (name "unconnected-(USB_TYPEC-CC1(A5)-Pad4)") (class "Default")
      (node (ref "USB_TYPEC") (pin "4") (pinfunction "CC1(A5)_4") (pintype "passive"))
    )
    (net (code "89") (name "unconnected-(USB_TYPEC-CC2(B5)-Pad10)") (class "Default")
      (node (ref "USB_TYPEC") (pin "10") (pinfunction "CC2(B5)_10") (pintype "passive"))
    )
    (net (code "90") (name "unconnected-(USB_TYPEC-SBU1(A8)-Pad9)") (class "Default")
      (node (ref "USB_TYPEC") (pin "9") (pinfunction "SBU1(A8)_9") (pintype "passive"))
    )
    (net (code "91") (name "unconnected-(USB_TYPEC-SBU2(B8)-Pad3)") (class "Default")
      (node (ref "USB_TYPEC") (pin "3") (pinfunction "SBU2(B8)_3") (pintype "passive"))
    )
  )
)
